# node_v1_1B.net
KiCad netlist of a schematic drawn in EAGLE
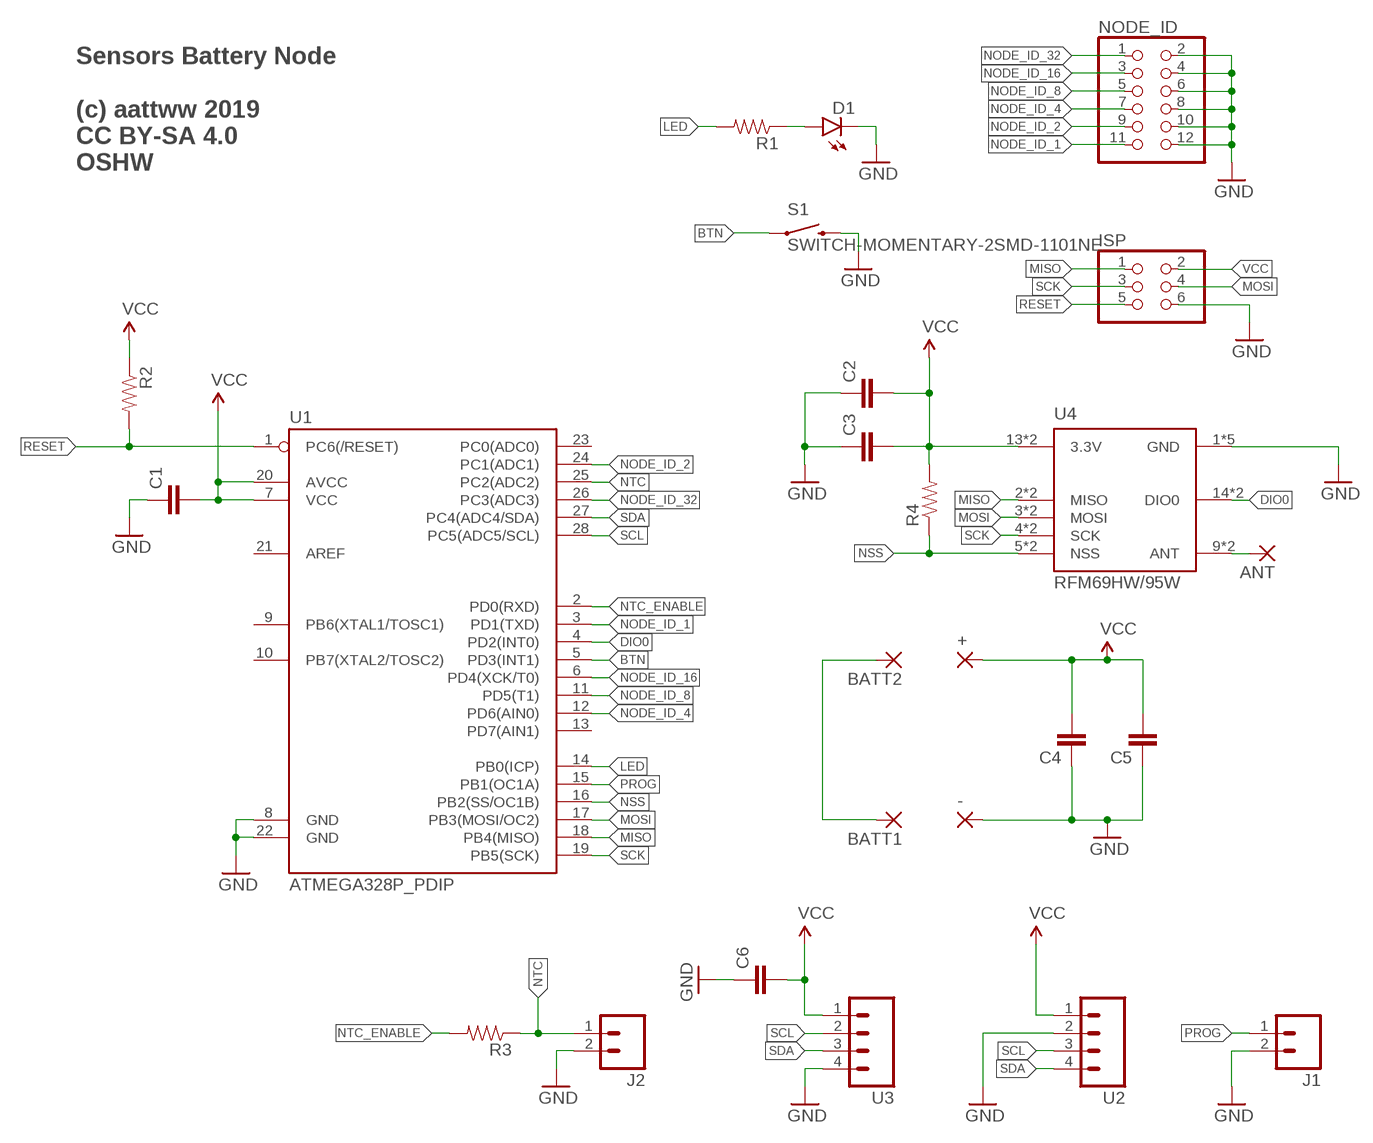
[diagram p0: schematic, sheet 1]

(export (version "E")
  (design (tool "Eeschema 10.0.6"))
  (components
    (comp (ref "+")
      (value "2,15/1,0")
      (footprint "eagle-import:2,15_1,0")
      (libsource (lib "eagle-import") (part "2,15/1,0"))
    )
    (comp (ref "-")
      (value "2,15/1,0")
      (footprint "eagle-import:2,15_1,0")
      (libsource (lib "eagle-import") (part "2,15/1,0"))
    )
    (comp (ref "ANT")
      (value "2,15/1,0")
      (footprint "eagle-import:2,15_1,0")
      (libsource (lib "eagle-import") (part "2,15/1,0"))
    )
    (comp (ref "BATT1")
      (value "2,15/1,0")
      (footprint "eagle-import:2,15_1,0")
      (libsource (lib "eagle-import") (part "2,15/1,0"))
    )
    (comp (ref "BATT2")
      (value "2,15/1,0")
      (footprint "eagle-import:2,15_1,0")
      (libsource (lib "eagle-import") (part "2,15/1,0"))
    )
    (comp (ref "C1")
      (value "CAP1206")
      (footprint "eagle-import:1206")
      (libsource (lib "eagle-import") (part "CAP1206"))
    )
    (comp (ref "C2")
      (value "CAP1206")
      (footprint "eagle-import:1206")
      (libsource (lib "eagle-import") (part "CAP1206"))
    )
    (comp (ref "C3")
      (value "CAP1206")
      (footprint "eagle-import:1206")
      (libsource (lib "eagle-import") (part "CAP1206"))
    )
    (comp (ref "C4")
      (value "CAP1206")
      (footprint "eagle-import:1206")
      (libsource (lib "eagle-import") (part "CAP1206"))
    )
    (comp (ref "C5")
      (value "CAP1206")
      (footprint "eagle-import:1206")
      (libsource (lib "eagle-import") (part "CAP1206"))
    )
    (comp (ref "C6")
      (value "CAP1206")
      (footprint "eagle-import:1206")
      (libsource (lib "eagle-import") (part "CAP1206"))
    )
    (comp (ref "D1")
      (value "LED1206")
      (footprint "eagle-import:LED-1206")
      (libsource (lib "eagle-import") (part "LED1206"))
    )
    (comp (ref "ISP")
      (value "PINHD-2X3")
      (footprint "eagle-import:2X03")
      (libsource (lib "eagle-import") (part "PINHD-2X3"))
    )
    (comp (ref "J1")
      (value "M02PTH")
      (footprint "eagle-import:1X02")
      (libsource (lib "eagle-import") (part "M02PTH"))
    )
    (comp (ref "J2")
      (value "M02PTH")
      (footprint "eagle-import:1X02")
      (libsource (lib "eagle-import") (part "M02PTH"))
    )
    (comp (ref "NODE_ID")
      (value "PINHD-2X6")
      (footprint "eagle-import:2X06")
      (libsource (lib "eagle-import") (part "PINHD-2X6"))
    )
    (comp (ref "R1")
      (value "RESISTOR1206")
      (footprint "eagle-import:1206")
      (libsource (lib "eagle-import") (part "RESISTOR1206"))
    )
    (comp (ref "R2")
      (value "RESISTOR1206")
      (footprint "eagle-import:1206")
      (libsource (lib "eagle-import") (part "RESISTOR1206"))
    )
    (comp (ref "R3")
      (value "RESISTOR1206")
      (footprint "eagle-import:1206")
      (libsource (lib "eagle-import") (part "RESISTOR1206"))
    )
    (comp (ref "R4")
      (value "RESISTOR1206")
      (footprint "eagle-import:1206")
      (libsource (lib "eagle-import") (part "RESISTOR1206"))
    )
    (comp (ref "S1")
      (value "SWITCH-MOMENTARY-2SMD-1101NE")
      (footprint "eagle-import:TACTILE-SWITCH-1101NE")
      (libsource (lib "eagle-import") (part "SWITCH-MOMENTARY-2SMD-1101NE"))
    )
    (comp (ref "U1")
      (value "ATMEGA328P_PDIP")
      (footprint "eagle-import:DIL28-3")
      (libsource (lib "eagle-import") (part "ATMEGA328P_PDIP"))
    )
    (comp (ref "U2")
      (value "M041X04_NO_SILK")
      (footprint "eagle-import:1X04_NO_SILK")
      (libsource (lib "eagle-import") (part "M041X04_NO_SILK"))
    )
    (comp (ref "U3")
      (value "M041X04_NO_SILK")
      (footprint "eagle-import:1X04_NO_SILK")
      (libsource (lib "eagle-import") (part "M041X04_NO_SILK"))
    )
    (comp (ref "U4")
      (value "RFM69HW/95W")
      (footprint "eagle-import:RFM69HW_95W")
      (libsource (lib "eagle-import") (part "RFM69HW/95W"))
    )
  )
  (nets
    (net (code "1") (name "BTN") (class "Default")
      (node (ref "S1") (pin "1") (pinfunction "1_1") (pintype "passive"))
      (node (ref "U1") (pin "5") (pinfunction "PD3(INT1)_5") (pintype "bidirectional"))
    )
    (net (code "2") (name "DIO0") (class "Default")
      (node (ref "U1") (pin "4") (pinfunction "PD2(INT0)_4") (pintype "bidirectional"))
      (node (ref "U4") (pin "14") (pinfunction "DIO0_14") (pintype "bidirectional"))
      (node (ref "U4") (pin "22") (pinfunction "DIO0_22") (pintype "bidirectional"))
    )
    (net (code "3") (name "GND") (class "Default")
      (node (ref "-") (pin "1") (pinfunction "P_1") (pintype "passive"))
      (node (ref "C1") (pin "1") (pinfunction "1_1") (pintype "passive"))
      (node (ref "C2") (pin "1") (pinfunction "1_1") (pintype "passive"))
      (node (ref "C3") (pin "1") (pinfunction "1_1") (pintype "passive"))
      (node (ref "C4") (pin "1") (pinfunction "1_1") (pintype "passive"))
      (node (ref "C5") (pin "1") (pinfunction "1_1") (pintype "passive"))
      (node (ref "C6") (pin "1") (pinfunction "1_1") (pintype "passive"))
      (node (ref "D1") (pin "C") (pinfunction "C_C") (pintype "passive"))
      (node (ref "ISP") (pin "6") (pinfunction "6_6") (pintype "passive"))
      (node (ref "J1") (pin "2") (pinfunction "2_2") (pintype "passive"))
      (node (ref "J2") (pin "2") (pinfunction "2_2") (pintype "passive"))
      (node (ref "NODE_ID") (pin "10") (pinfunction "10_10") (pintype "passive"))
      (node (ref "NODE_ID") (pin "12") (pinfunction "12_12") (pintype "passive"))
      (node (ref "NODE_ID") (pin "2") (pinfunction "2_2") (pintype "passive"))
      (node (ref "NODE_ID") (pin "4") (pinfunction "4_4") (pintype "passive"))
      (node (ref "NODE_ID") (pin "6") (pinfunction "6_6") (pintype "passive"))
      (node (ref "NODE_ID") (pin "8") (pinfunction "8_8") (pintype "passive"))
      (node (ref "S1") (pin "2") (pinfunction "2_2") (pintype "passive"))
      (node (ref "U1") (pin "22") (pinfunction "GND_22") (pintype "bidirectional"))
      (node (ref "U1") (pin "8") (pinfunction "GND_8") (pintype "bidirectional"))
      (node (ref "U2") (pin "2") (pinfunction "2_2") (pintype "passive"))
      (node (ref "U3") (pin "4") (pinfunction "4_4") (pintype "passive"))
      (node (ref "U4") (pin "1") (pinfunction "GND_1") (pintype "power_in"))
      (node (ref "U4") (pin "10") (pinfunction "GND_10") (pintype "power_in"))
      (node (ref "U4") (pin "29") (pinfunction "GND_29") (pintype "power_in"))
      (node (ref "U4") (pin "31") (pinfunction "GND_31") (pintype "power_in"))
      (node (ref "U4") (pin "8") (pinfunction "GND_8") (pintype "power_in"))
    )
    (net (code "4") (name "LED") (class "Default")
      (node (ref "R1") (pin "2") (pinfunction "2_2") (pintype "passive"))
      (node (ref "U1") (pin "14") (pinfunction "PB0(ICP)_14") (pintype "bidirectional"))
    )
    (net (code "5") (name "MISO") (class "Default")
      (node (ref "ISP") (pin "1") (pinfunction "1_1") (pintype "passive"))
      (node (ref "U1") (pin "18") (pinfunction "PB4(MISO)_18") (pintype "bidirectional"))
      (node (ref "U4") (pin "2") (pinfunction "MISO_2") (pintype "bidirectional"))
      (node (ref "U4") (pin "33") (pinfunction "MISO_33") (pintype "bidirectional"))
    )
    (net (code "6") (name "MOSI") (class "Default")
      (node (ref "ISP") (pin "4") (pinfunction "4_4") (pintype "passive"))
      (node (ref "U1") (pin "17") (pinfunction "PB3(MOSI/OC2)_17") (pintype "bidirectional"))
      (node (ref "U4") (pin "3") (pinfunction "MOSI_3") (pintype "input"))
      (node (ref "U4") (pin "34") (pinfunction "MOSI_34") (pintype "input"))
    )
    (net (code "7") (name "NODE_ID_1") (class "Default")
      (node (ref "NODE_ID") (pin "11") (pinfunction "11_11") (pintype "passive"))
      (node (ref "U1") (pin "3") (pinfunction "PD1(TXD)_3") (pintype "bidirectional"))
    )
    (net (code "8") (name "NODE_ID_2") (class "Default")
      (node (ref "NODE_ID") (pin "9") (pinfunction "9_9") (pintype "passive"))
      (node (ref "U1") (pin "24") (pinfunction "PC1(ADC1)_24") (pintype "bidirectional"))
    )
    (net (code "9") (name "NODE_ID_4") (class "Default")
      (node (ref "NODE_ID") (pin "7") (pinfunction "7_7") (pintype "passive"))
      (node (ref "U1") (pin "12") (pinfunction "PD6(AIN0)_12") (pintype "bidirectional"))
    )
    (net (code "10") (name "NODE_ID_8") (class "Default")
      (node (ref "NODE_ID") (pin "5") (pinfunction "5_5") (pintype "passive"))
      (node (ref "U1") (pin "11") (pinfunction "PD5(T1)_11") (pintype "bidirectional"))
    )
    (net (code "11") (name "NODE_ID_16") (class "Default")
      (node (ref "NODE_ID") (pin "3") (pinfunction "3_3") (pintype "passive"))
      (node (ref "U1") (pin "6") (pinfunction "PD4(XCK/T0)_6") (pintype "bidirectional"))
    )
    (net (code "12") (name "NODE_ID_32") (class "Default")
      (node (ref "NODE_ID") (pin "1") (pinfunction "1_1") (pintype "passive"))
      (node (ref "U1") (pin "26") (pinfunction "PC3(ADC3)_26") (pintype "bidirectional"))
    )
    (net (code "13") (name "NSS") (class "Default")
      (node (ref "R4") (pin "1") (pinfunction "1_1") (pintype "passive"))
      (node (ref "U1") (pin "16") (pinfunction "PB2(SS/OC1B)_16") (pintype "bidirectional"))
      (node (ref "U4") (pin "35") (pinfunction "NSS_35") (pintype "input"))
      (node (ref "U4") (pin "5") (pinfunction "NSS_5") (pintype "input"))
    )
    (net (code "14") (name "NTC") (class "Default")
      (node (ref "J2") (pin "1") (pinfunction "1_1") (pintype "passive"))
      (node (ref "R3") (pin "1") (pinfunction "1_1") (pintype "passive"))
      (node (ref "U1") (pin "25") (pinfunction "PC2(ADC2)_25") (pintype "bidirectional"))
    )
    (net (code "15") (name "NTC_ENABLE") (class "Default")
      (node (ref "R3") (pin "2") (pinfunction "2_2") (pintype "passive"))
      (node (ref "U1") (pin "2") (pinfunction "PD0(RXD)_2") (pintype "bidirectional"))
    )
    (net (code "16") (name "Net-(ANT-P)") (class "Default")
      (node (ref "ANT") (pin "1") (pinfunction "P_1") (pintype "passive"))
      (node (ref "U4") (pin "30") (pinfunction "ANT_30") (pintype "passive"))
      (node (ref "U4") (pin "9") (pinfunction "ANT_9") (pintype "passive"))
    )
    (net (code "17") (name "Net-(BATT1-P)") (class "Default")
      (node (ref "BATT1") (pin "1") (pinfunction "P_1") (pintype "passive"))
      (node (ref "BATT2") (pin "1") (pinfunction "P_1") (pintype "passive"))
    )
    (net (code "18") (name "Net-(D1-PadA)") (class "Default")
      (node (ref "D1") (pin "A") (pinfunction "A_A") (pintype "passive"))
      (node (ref "R1") (pin "1") (pinfunction "1_1") (pintype "passive"))
    )
    (net (code "19") (name "PROG") (class "Default")
      (node (ref "J1") (pin "1") (pinfunction "1_1") (pintype "passive"))
      (node (ref "U1") (pin "15") (pinfunction "PB1(OC1A)_15") (pintype "bidirectional"))
    )
    (net (code "20") (name "RESET") (class "Default")
      (node (ref "ISP") (pin "5") (pinfunction "5_5") (pintype "passive"))
      (node (ref "R2") (pin "2") (pinfunction "2_2") (pintype "passive"))
      (node (ref "U1") (pin "1") (pinfunction "PC6(/RESET)_1") (pintype "bidirectional"))
    )
    (net (code "21") (name "SCK") (class "Default")
      (node (ref "ISP") (pin "3") (pinfunction "3_3") (pintype "passive"))
      (node (ref "U1") (pin "19") (pinfunction "PB5(SCK)_19") (pintype "bidirectional"))
      (node (ref "U4") (pin "32") (pinfunction "SCK_32") (pintype "input"))
      (node (ref "U4") (pin "4") (pinfunction "SCK_4") (pintype "input"))
    )
    (net (code "22") (name "SCL") (class "Default")
      (node (ref "U1") (pin "28") (pinfunction "PC5(ADC5/SCL)_28") (pintype "bidirectional"))
      (node (ref "U2") (pin "3") (pinfunction "3_3") (pintype "passive"))
      (node (ref "U3") (pin "2") (pinfunction "2_2") (pintype "passive"))
    )
    (net (code "23") (name "SDA") (class "Default")
      (node (ref "U1") (pin "27") (pinfunction "PC4(ADC4/SDA)_27") (pintype "bidirectional"))
      (node (ref "U2") (pin "4") (pinfunction "4_4") (pintype "passive"))
      (node (ref "U3") (pin "3") (pinfunction "3_3") (pintype "passive"))
    )
    (net (code "24") (name "VCC") (class "Default")
      (node (ref "+") (pin "1") (pinfunction "P_1") (pintype "passive"))
      (node (ref "C1") (pin "2") (pinfunction "2_2") (pintype "passive"))
      (node (ref "C2") (pin "2") (pinfunction "2_2") (pintype "passive"))
      (node (ref "C3") (pin "2") (pinfunction "2_2") (pintype "passive"))
      (node (ref "C4") (pin "2") (pinfunction "2_2") (pintype "passive"))
      (node (ref "C5") (pin "2") (pinfunction "2_2") (pintype "passive"))
      (node (ref "C6") (pin "2") (pinfunction "2_2") (pintype "passive"))
      (node (ref "ISP") (pin "2") (pinfunction "2_2") (pintype "passive"))
      (node (ref "R2") (pin "1") (pinfunction "1_1") (pintype "passive"))
      (node (ref "R4") (pin "2") (pinfunction "2_2") (pintype "passive"))
      (node (ref "U1") (pin "20") (pinfunction "AVCC_20") (pintype "bidirectional"))
      (node (ref "U1") (pin "7") (pinfunction "VCC_7") (pintype "bidirectional"))
      (node (ref "U2") (pin "1") (pinfunction "1_1") (pintype "passive"))
      (node (ref "U3") (pin "1") (pinfunction "1_1") (pintype "passive"))
      (node (ref "U4") (pin "13") (pinfunction "3.3V_13") (pintype "power_in"))
      (node (ref "U4") (pin "28") (pinfunction "3.3V_28") (pintype "power_in"))
    )
    (net (code "25") (name "unconnected-(U1-AREF-Pad21)") (class "Default")
      (node (ref "U1") (pin "21") (pinfunction "AREF_21") (pintype "bidirectional"))
    )
    (net (code "26") (name "unconnected-(U1-PB6(XTAL1{slash}TOSC1)-Pad9)") (class "Default")
      (node (ref "U1") (pin "9") (pinfunction "PB6(XTAL1/TOSC1)_9") (pintype "bidirectional"))
    )
    (net (code "27") (name "unconnected-(U1-PB7(XTAL2{slash}TOSC2)-Pad10)") (class "Default")
      (node (ref "U1") (pin "10") (pinfunction "PB7(XTAL2/TOSC2)_10") (pintype "bidirectional"))
    )
    (net (code "28") (name "unconnected-(U1-PC0(ADC0)-Pad23)") (class "Default")
      (node (ref "U1") (pin "23") (pinfunction "PC0(ADC0)_23") (pintype "bidirectional"))
    )
    (net (code "29") (name "unconnected-(U1-PD7(AIN1)-Pad13)") (class "Default")
      (node (ref "U1") (pin "13") (pinfunction "PD7(AIN1)_13") (pintype "bidirectional"))
    )
  )
)
